# KeyBoard.net
KiCad netlist of a schematic drawn in Altium Designer
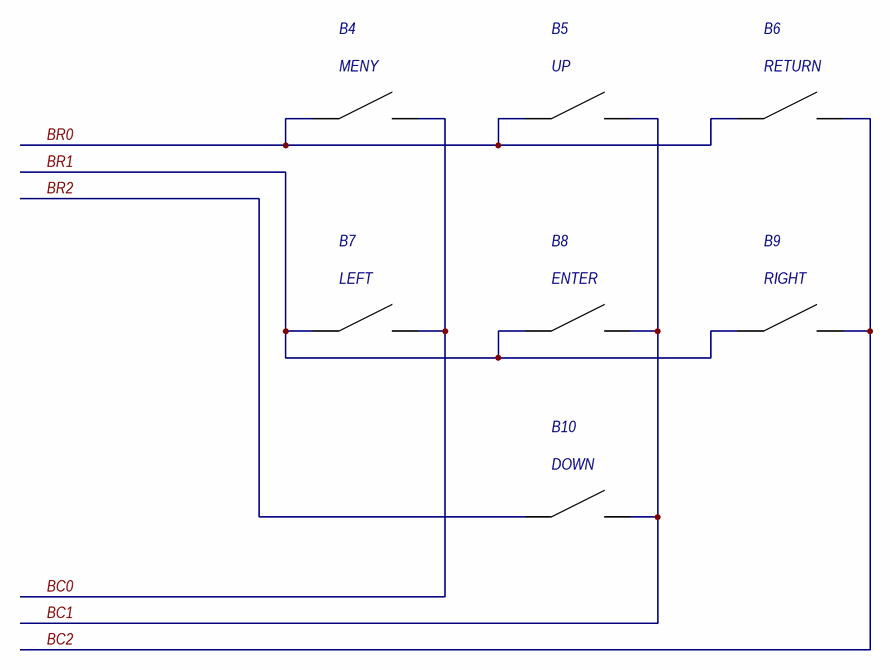
[diagram p0: KeyBoard.SchDoc]

(export (version "E")
  (design (tool "Eeschema 10.0.6"))
  (components
    (comp (ref "B4") (value "BUTTON") (footprint "BUTTON_DIP") (libsource (lib "my_lib") (part "BUTTON")))
    (comp (ref "B5") (value "BUTTON") (footprint "BUTTON_DIP") (libsource (lib "my_lib") (part "BUTTON")))
    (comp (ref "B6") (value "BUTTON") (footprint "BUTTON_DIP") (libsource (lib "my_lib") (part "BUTTON")))
    (comp (ref "B7") (value "BUTTON") (footprint "BUTTON_DIP") (libsource (lib "my_lib") (part "BUTTON")))
    (comp (ref "B8") (value "BUTTON") (footprint "BUTTON_DIP") (libsource (lib "my_lib") (part "BUTTON")))
    (comp (ref "B9") (value "BUTTON") (footprint "BUTTON_DIP") (libsource (lib "my_lib") (part "BUTTON")))
    (comp (ref "B10") (value "BUTTON") (footprint "BUTTON_DIP") (libsource (lib "my_lib") (part "BUTTON")))
  )
  (nets
    (net (code "1") (name "/BC0") (class "Default")
      (node (ref "B4") (pin "2") (pinfunction "2_2") (pintype "passive"))
      (node (ref "B7") (pin "2") (pinfunction "2_2") (pintype "passive"))
    )
    (net (code "2") (name "/BC1") (class "Default")
      (node (ref "B10") (pin "2") (pinfunction "2_2") (pintype "passive"))
      (node (ref "B5") (pin "2") (pinfunction "2_2") (pintype "passive"))
      (node (ref "B8") (pin "2") (pinfunction "2_2") (pintype "passive"))
    )
    (net (code "3") (name "/BC2") (class "Default")
      (node (ref "B6") (pin "2") (pinfunction "2_2") (pintype "passive"))
      (node (ref "B9") (pin "2") (pinfunction "2_2") (pintype "passive"))
    )
    (net (code "4") (name "/BR0") (class "Default")
      (node (ref "B4") (pin "1") (pinfunction "1_1") (pintype "passive"))
      (node (ref "B5") (pin "1") (pinfunction "1_1") (pintype "passive"))
      (node (ref "B6") (pin "1") (pinfunction "1_1") (pintype "passive"))
    )
    (net (code "5") (name "/BR1") (class "Default")
      (node (ref "B7") (pin "1") (pinfunction "1_1") (pintype "passive"))
      (node (ref "B8") (pin "1") (pinfunction "1_1") (pintype "passive"))
      (node (ref "B9") (pin "1") (pinfunction "1_1") (pintype "passive"))
    )
    (net (code "6") (name "/BR2") (class "Default")
      (node (ref "B10") (pin "1") (pinfunction "1_1") (pintype "passive"))
    )
  )
)
